# RefPoint01-01.net
KiCad netlist of a schematic drawn in Altium Designer
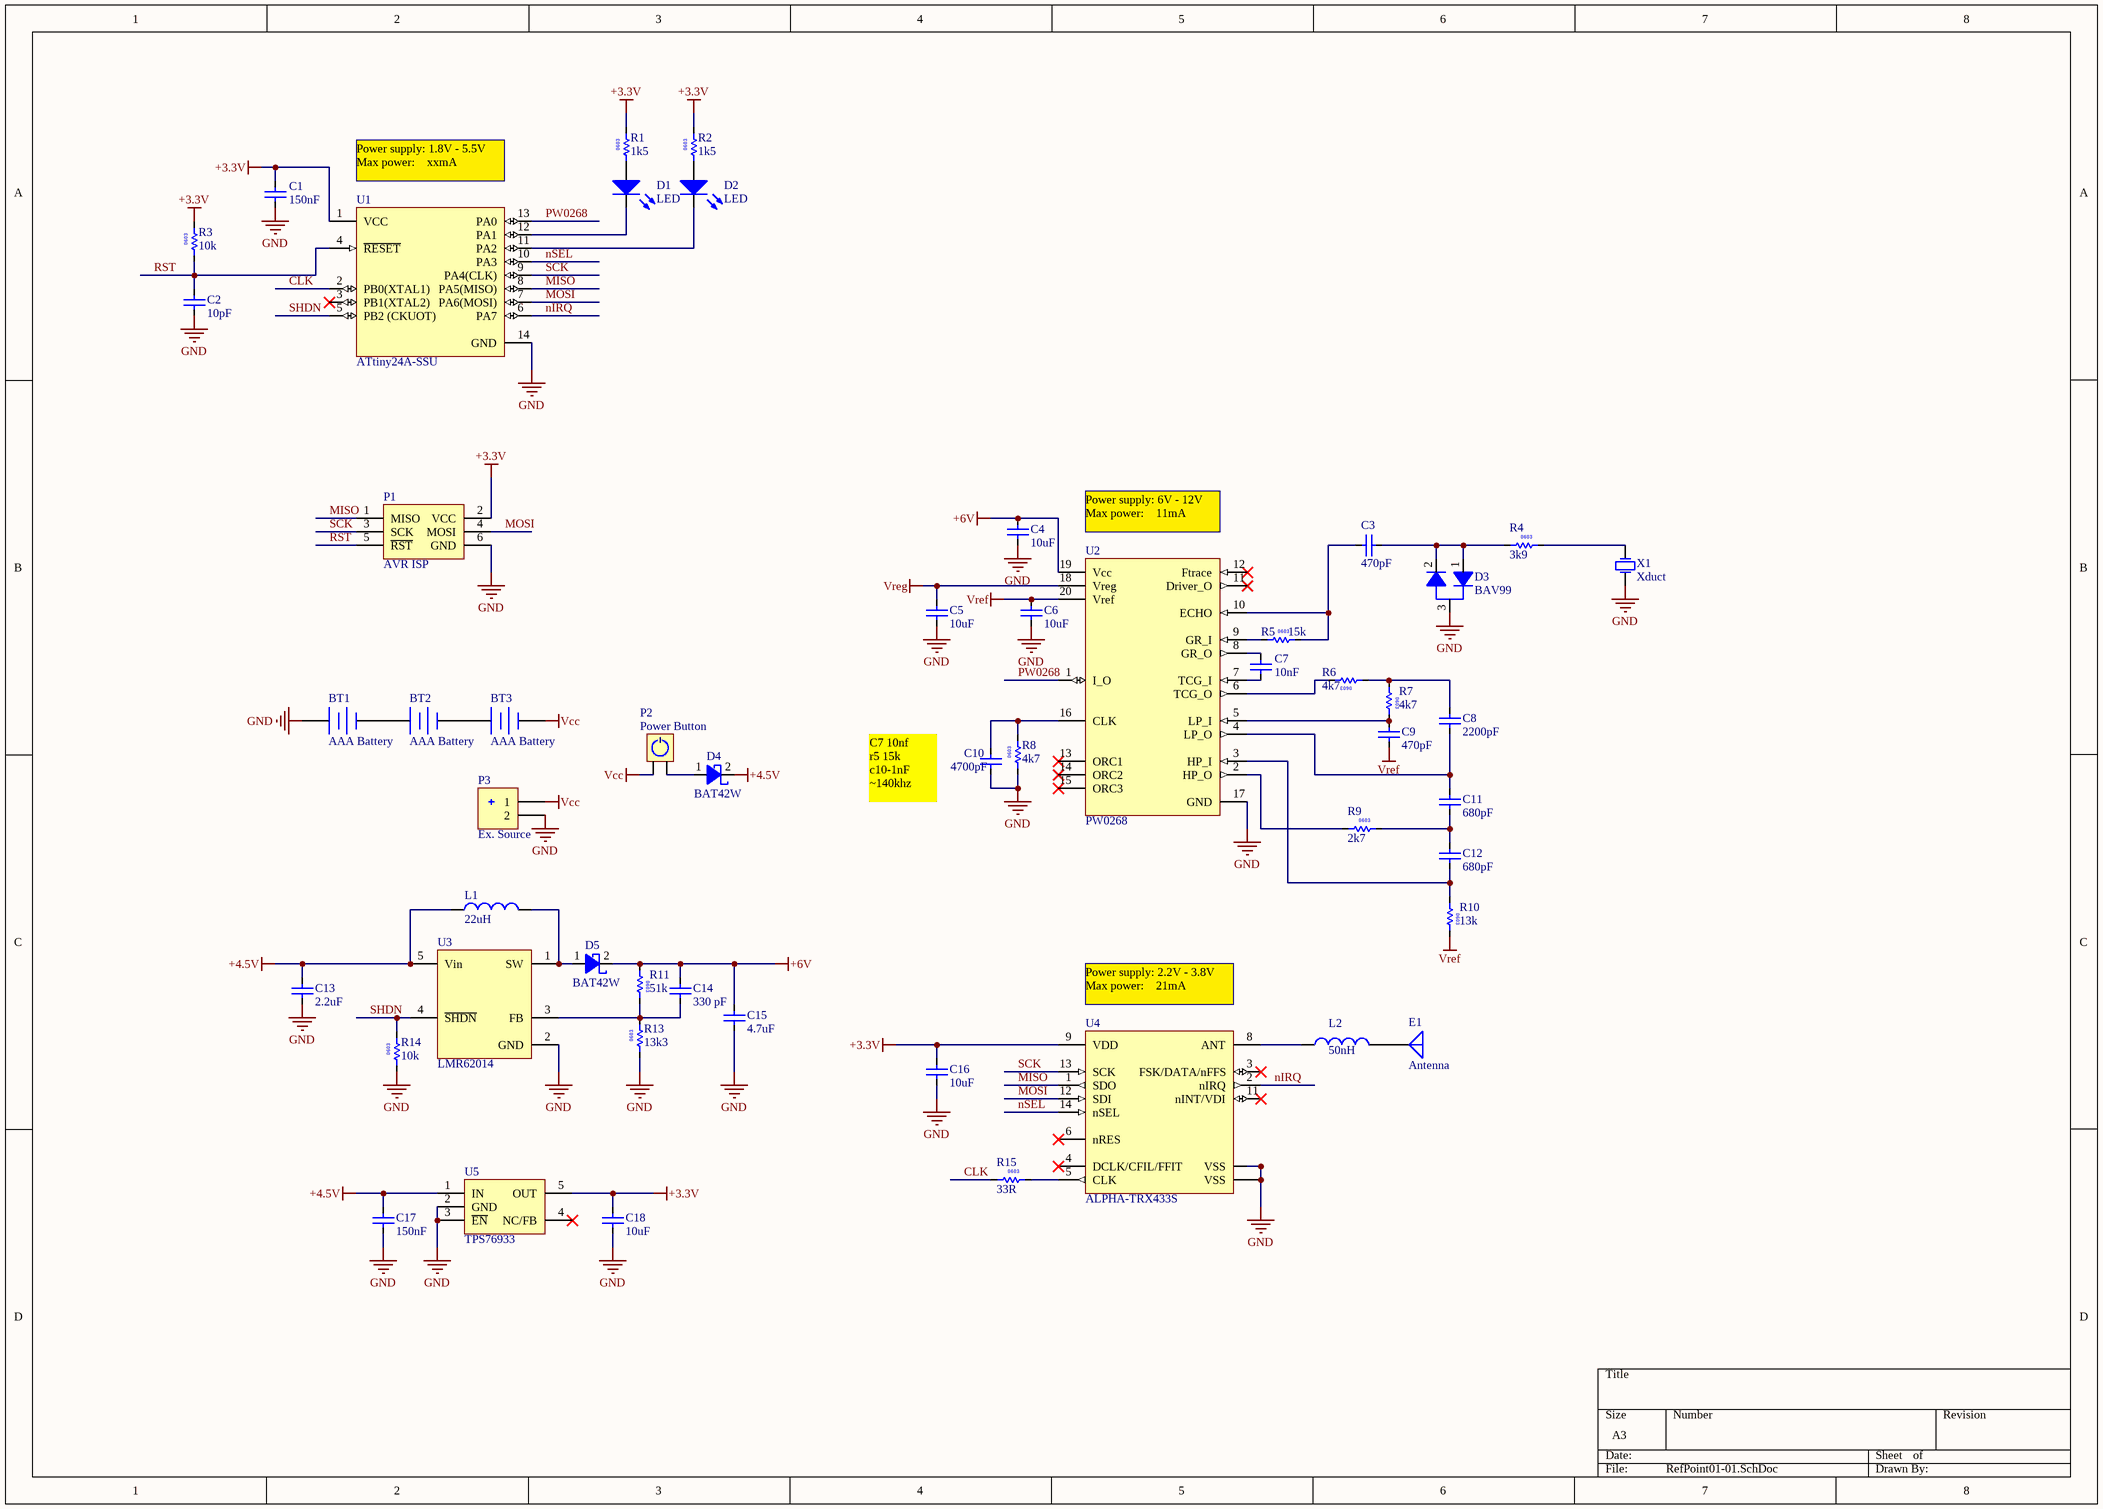
[diagram p0: RefPoint01-01.SchDoc]

(export (version "E")
  (design (tool "Eeschema 10.0.6"))
  (components
    (comp (ref "BT1")
      (value "AAA Battery")
      (footprint "Keystone 55 AAA CLIP")
      (description "Battery AAA")
      (fields (field (name "MANUFACTURER") "KEYSTONE") (field (name "MANUFACTURER PART NUMBER") "55"))
      (libsource (lib "UserSchlib") (part "Battery_AAA"))
    )
    (comp (ref "BT2")
      (value "AAA Battery")
      (footprint "Keystone 55 AAA CLIP")
      (description "Battery AAA")
      (fields (field (name "MANUFACTURER") "KEYSTONE") (field (name "MANUFACTURER PART NUMBER") "55"))
      (libsource (lib "UserSchlib") (part "Battery_AAA"))
    )
    (comp (ref "BT3")
      (value "AAA Battery")
      (footprint "Keystone 55 AAA CLIP")
      (description "Battery AAA")
      (fields (field (name "MANUFACTURER") "KEYSTONE") (field (name "MANUFACTURER PART NUMBER") "55"))
      (libsource (lib "UserSchlib") (part "Battery_AAA"))
    )
    (comp (ref "C1")
      (value "150nF")
      (footprint "CAPC1608N")
      (description "MLCC, 150nF 16V -20+80% Y5V")
      (fields (field (name "PART NUMBER") "C0000001") (field (name "VOLTAGE") "16"))
      (libsource (lib "KTU_DB") (part "C_SM"))
    )
    (comp (ref "C2")
      (value "10pF")
      (footprint "CAPC1608N")
      (description "MLCC, 0603, NP0, 50V, 10PF")
      (fields (field (name "PART NUMBER") "C0000042") (field (name "VOLTAGE") "100"))
      (libsource (lib "KTU_DB") (part "C_SM"))
    )
    (comp (ref "C3")
      (value "470pF")
      (footprint "CAPC1608N")
      (description "MLCC, 470pF 50V C0G 5% 0603")
      (fields (field (name "PART NUMBER") "C0000062") (field (name "VOLTAGE") "50"))
      (libsource (lib "KTU_DB") (part "C_SM"))
    )
    (comp (ref "C4")
      (value "10uF")
      (footprint "CAPC3216N")
      (description "MLCC, 10uF 25V -20%, +80% Y5V 1206")
      (fields (field (name "PART NUMBER") "C0000011") (field (name "VOLTAGE") "25"))
      (libsource (lib "KTU_DB") (part "C_SM"))
    )
    (comp (ref "C5")
      (value "10uF")
      (footprint "CAPC3216N")
      (description "MLCC, 10uF 25V -20%, +80% Y5V 1206")
      (fields (field (name "PART NUMBER") "C0000011") (field (name "VOLTAGE") "25"))
      (libsource (lib "KTU_DB") (part "C_SM"))
    )
    (comp (ref "C6")
      (value "10uF")
      (footprint "CAPC3216N")
      (description "MLCC, 10uF 25V -20%, +80% Y5V 1206")
      (fields (field (name "PART NUMBER") "C0000011") (field (name "VOLTAGE") "25"))
      (libsource (lib "KTU_DB") (part "C_SM"))
    )
    (comp (ref "C7")
      (value "10nF")
      (footprint "CAPC1608N")
      (description "MLCC, 0603, NP0, 50V, 10PF")
      (fields (field (name "PART NUMBER") "C0000042") (field (name "VOLTAGE") "100"))
      (libsource (lib "KTU_DB") (part "C_SM"))
    )
    (comp (ref "C8")
      (value "2200pF")
      (footprint "CAPC1608N")
      (description "MLCC, 2200pF 50V X7R 5% 0603")
      (fields (field (name "PART NUMBER") "C0000126") (field (name "VOLTAGE") "50"))
      (libsource (lib "KTU_DB") (part "C_SM"))
    )
    (comp (ref "C9")
      (value "470pF")
      (footprint "CAPC1608N")
      (description "MLCC, 470pF 50V C0G 5% 0603")
      (fields (field (name "PART NUMBER") "C0000062") (field (name "VOLTAGE") "50"))
      (libsource (lib "KTU_DB") (part "C_SM"))
    )
    (comp (ref "C10")
      (value "4700pF")
      (footprint "CAPC1608N")
      (description "MLCC, 4700pF 50V X7R 5% 0603")
      (fields (field (name "PART NUMBER") "C0000127") (field (name "VOLTAGE") "50"))
      (libsource (lib "KTU_DB") (part "C_SM"))
    )
    (comp (ref "C11")
      (value "680pF")
      (footprint "CAPC1608N")
      (description "MLCC, 680pF 50V C0G / NP0 5% 0603")
      (fields (field (name "PART NUMBER") "C0000125") (field (name "VOLTAGE") "50"))
      (libsource (lib "KTU_DB") (part "C_SM"))
    )
    (comp (ref "C12")
      (value "680pF")
      (footprint "CAPC1608N")
      (description "MLCC, 680pF 50V C0G / NP0 5% 0603")
      (fields (field (name "PART NUMBER") "C0000125") (field (name "VOLTAGE") "50"))
      (libsource (lib "KTU_DB") (part "C_SM"))
    )
    (comp (ref "C13")
      (value "2.2uF")
      (footprint "CAPC2012N")
      (description "MLCC, 2.2uF 16V X7R 0805")
      (fields (field (name "PART NUMBER") "C0000129") (field (name "VOLTAGE") "16V"))
      (libsource (lib "KTU_DB") (part "C_SM"))
    )
    (comp (ref "C14")
      (value "330 pF")
      (footprint "CAPC1608N")
      (description "MLCC, 50V, 330pF, 10%, X7R, 0603")
      (fields (field (name "PART NUMBER") "C0000018") (field (name "VOLTAGE") "50"))
      (libsource (lib "KTU_DB") (part "C_SM"))
    )
    (comp (ref "C15")
      (value "4.7uF")
      (footprint "CAPC3225N")
      (description "MLCC, 4.7uF 16V X7R 1210")
      (fields (field (name "PART NUMBER") "C0000130") (field (name "VOLTAGE") "50V"))
      (libsource (lib "KTU_DB") (part "C_SM"))
    )
    (comp (ref "C16")
      (value "10uF")
      (footprint "CAPC3216N")
      (description "MLCC, 10uF 25V -20%, +80% Y5V 1206")
      (fields (field (name "PART NUMBER") "C0000011") (field (name "VOLTAGE") "25"))
      (libsource (lib "KTU_DB") (part "C_SM"))
    )
    (comp (ref "C17")
      (value "150nF")
      (footprint "CAPC1608N")
      (description "MLCC, 150nF 16V -20+80% Y5V")
      (fields (field (name "PART NUMBER") "C0000001") (field (name "VOLTAGE") "16"))
      (libsource (lib "KTU_DB") (part "C_SM"))
    )
    (comp (ref "C18")
      (value "10uF")
      (footprint "CAPC3216N")
      (description "MLCC, 10uF 25V -20%, +80% Y5V 1206")
      (fields (field (name "PART NUMBER") "C0000011") (field (name "VOLTAGE") "25"))
      (libsource (lib "KTU_DB") (part "C_SM"))
    )
    (comp (ref "D1")
      (value "LED")
      (footprint "LED 3mm DIP")
      (description "Typical INFRARED GaAs LED")
      (fields (field (name "PUBLISHER") "Altium Limited"))
      (libsource (lib "UserSchlib") (part "LED0"))
    )
    (comp (ref "D2")
      (value "LED")
      (footprint "LED 3mm DIP")
      (description "Typical INFRARED GaAs LED")
      (fields (field (name "PUBLISHER") "Altium Limited"))
      (libsource (lib "UserSchlib") (part "LED0"))
    )
    (comp (ref "D3")
      (value "BAV99")
      (footprint "SOT95P240-3L")
      (description "DIODE SW DUAL 75V 350mW SOT23")
      (fields (field (name "PART NUMBER") "D0000001") (field (name "MANUFACTURER") "ON SEMICONDUCTOR"))
      (libsource (lib "KTU_DB") (part "BAV99"))
    )
    (comp (ref "D4")
      (value "BAT42W")
      (footprint "SOD123")
      (description "Diode Schottkey, 30V, Vf=1V, If=1A, rrt=5ns, SOD123, -55°C to +125°C")
      (fields (field (name "PART NUMBER") "D0000003") (field (name "MANUFACTURER") "VISHAY SEMICONDUCTOR"))
      (libsource (lib "KTU_DB") (part "Diode_SCHOTTKY"))
    )
    (comp (ref "D5")
      (value "BAT42W")
      (footprint "SOD123")
      (description "Diode Schottkey, 30V, Vf=1V, If=1A, rrt=5ns, SOD123, -55°C to +125°C")
      (fields (field (name "PART NUMBER") "D0000003") (field (name "MANUFACTURER") "VISHAY SEMICONDUCTOR"))
      (libsource (lib "KTU_DB") (part "Diode_SCHOTTKY"))
    )
    (comp (ref "E1")
      (value "Antenna")
      (description "Generic Antenna")
      (fields (field (name "PUBLISHER") "Altium Limited"))
      (libsource (lib "Miscellaneous Devices") (part "Antenna"))
    )
    (comp (ref "L1")
      (value "22uH")
      (footprint "INDM7070x32N")
      (description "Inductor")
      (fields
        (field (name "MANUFACTURER PART NUMBER") "810-SLF732220MR962PF")
        (field (name "MANUFACTURER") "TDK")
      )
      (libsource (lib "UserSchlib") (part "L Inductor 810-SLF732220MR962PF"))
    )
    (comp (ref "L2")
      (value "50nH")
      (footprint "INDC2012L")
      (description "Inductor")
      (fields (field (name "PUBLISHER") "Altium Limited"))
      (libsource (lib "Miscellaneous Devices") (part "Inductor"))
    )
    (comp (ref "P1")
      (value "AVR ISP")
      (footprint "HDR2X3")
      (description "Header, 6-Pin")
      (fields (field (name "PUBLISHER") "Altium Limited"))
      (libsource (lib "Arthur Shematic") (part "AVR ISP"))
    )
    (comp (ref "P2")
      (value "Power Button")
      (footprint "HDR1X2")
      (description "Header, 2-Pin, Right Angle")
      (fields (field (name "PUBLISHER") "Altium Limited"))
      (libsource (lib "UserSchlib") (part "Power Button"))
    )
    (comp (ref "P3")
      (value "Ex. Source")
      (footprint "HDR1X2")
      (description "Header, 2-Pin")
      (fields (field (name "PUBLISHER") "Altium Limited"))
      (libsource (lib "Arthur Shematic") (part "Maitinimas"))
    )
    (comp (ref "R1")
      (value "1k5")
      (footprint "RESC1608N")
      (description "1K5 5% 0603 1/10W")
      (fields (field (name "TOLERANCE") "±5%") (field (name "POWER") "1/10W"))
      (libsource (lib "KTU_DB") (part "R0603"))
    )
    (comp (ref "R2")
      (value "1k5")
      (footprint "RESC1608N")
      (description "1K5 5% 0603 1/10W")
      (fields (field (name "TOLERANCE") "±5%") (field (name "POWER") "1/10W"))
      (libsource (lib "KTU_DB") (part "R0603"))
    )
    (comp (ref "R3")
      (value "10k")
      (footprint "RESC1608N")
      (description "Res, 10K 0.063W 75V 1%  0603")
      (fields (field (name "TOLERANCE") "±1%") (field (name "POWER") "0.063W"))
      (libsource (lib "KTU_DB") (part "R0603"))
    )
    (comp (ref "R4")
      (value "3k9")
      (footprint "RESC1608N")
      (description "3K9 5% 0603 1/10W")
      (fields (field (name "TOLERANCE") "±5%") (field (name "POWER") "1/10W"))
      (libsource (lib "KTU_DB") (part "R0603"))
    )
    (comp (ref "R5")
      (value "15k")
      (footprint "RESC1608N")
      (description "300K 5% 0603 1/10W")
      (fields (field (name "TOLERANCE") "±5%") (field (name "POWER") "1/10W"))
      (libsource (lib "KTU_DB") (part "R0603"))
    )
    (comp (ref "R6")
      (value "4k7")
      (footprint "RESC1608N")
      (description "Res, 4K7 5% 0603 1/10W")
      (fields (field (name "TOLERANCE") "±5%") (field (name "POWER") "1/10W"))
      (libsource (lib "KTU_DB") (part "R0603"))
    )
    (comp (ref "R7")
      (value "4k7")
      (footprint "RESC1608N")
      (description "Res, 4K7 5% 0603 1/10W")
      (fields (field (name "TOLERANCE") "±5%") (field (name "POWER") "1/10W"))
      (libsource (lib "KTU_DB") (part "R0603"))
    )
    (comp (ref "R8")
      (value "4k7")
      (footprint "RESC1608N")
      (description "Res, 4K7 5% 0603 1/10W")
      (fields (field (name "TOLERANCE") "±5%") (field (name "POWER") "1/10W"))
      (libsource (lib "KTU_DB") (part "R0603"))
    )
    (comp (ref "R9")
      (value "2k7")
      (footprint "RESC1608N")
      (description "2K7 5% 0603 1/10W")
      (fields (field (name "TOLERANCE") "±5%") (field (name "POWER") "1/10W"))
      (libsource (lib "KTU_DB") (part "R0603"))
    )
    (comp (ref "R10")
      (value "13k")
      (footprint "RESC1608N")
      (description "13K 5% 0603 1/10W")
      (fields (field (name "TOLERANCE") "±5%") (field (name "POWER") "1/10W"))
      (libsource (lib "KTU_DB") (part "R0603"))
    )
    (comp (ref "R11")
      (value "51k")
      (footprint "RESC1608X50N")
      (description "Res, 51K, 0603 (1608 metric), ±1%, 100mW, 75V")
      (fields (field (name "TOLERANCE") "±1%") (field (name "POWER") "100mW"))
      (libsource (lib "KTU_DB") (part "R0603"))
    )
    (comp (ref "R13")
      (value "13k3")
      (footprint "RESC1608X50N")
      (description "Res, 13K3, 0603 (1608 metric), ±1%, 100mW, 75V")
      (fields (field (name "TOLERANCE") "±1%") (field (name "POWER") "100mW"))
      (libsource (lib "KTU_DB") (part "R0603"))
    )
    (comp (ref "R14")
      (value "10k")
      (footprint "RESC1608X50N")
      (description "Res, 10K, 0603 (1608 metric), ±1%, 100mW, 75V")
      (libsource (lib "KTU_DB") (part "R0603"))
    )
    (comp (ref "R15")
      (value "33R")
      (footprint "RESC1608X50N")
      (description "Res, 33R, 0603 (1608 metric), ±1%, 100mW, 75V")
      (libsource (lib "KTU_DB") (part "R0603"))
    )
    (comp (ref "U1")
      (value "ATtiny24A-SSU")
      (footprint "UserPcbLib:SOIC14T_L")
      (fields (field (name "MANUFACTURER") "Atmel"))
      (libsource (lib "UserSchlib") (part "ATtiny24A-SSU"))
    )
    (comp (ref "U2")
      (value "PW0268")
      (footprint "QSSOP20_0.635/4.0X8.7")
      (fields (field (name "MANUFACTURER") "PROWAVE"))
      (libsource (lib "UserSchlib") (part "PW0268"))
    )
    (comp (ref "U3")
      (value "LMR62014")
      (footprint "SOT23-5AM")
      (description "2064695")
      (fields
        (field (name "MANUFACTURER PART NUMBER") "LMR62014XMFE")
        (field (name "MANUFACTURER") "TEXAS INSTRUMENTS")
      )
      (libsource (lib "UserSchlib") (part "LMR62014"))
    )
    (comp (ref "U4")
      (value "ALPHA-TRX433S")
      (footprint "ALPHA-TRX")
      (description "RF SOLUTIONS  ALPHA-TRX433S  RF MODULE, TRANSCEIVER, FSK, 433MHZ")
      (fields (field (name "MANUFACTURER") "RF SOLUTIONS"))
      (libsource (lib "UserSchlib") (part "ALPHA-TRX433S"))
    )
    (comp (ref "U5")
      (value "TPS76933")
      (footprint "SOT23-5AM")
      (description "ULTRALOW-POWER 100-mA LOW-DROPOUT LINEAR REGULATORS")
      (fields
        (field (name "MANUFACTURER PART NUMBER") "TPS76933DBVT")
        (field (name "MANUFACTURER") "TEXAS INSTRUMENTS")
      )
      (libsource (lib "UserSchlib") (part "TPS769xx"))
    )
    (comp (ref "X1")
      (value "Xduct")
      (footprint "Xducts1")
      (description "Transducer")
      (libsource (lib "UserSchlib") (part "Xduct1"))
    )
  )
  (nets
    (net (code "1") (name "+3.3V") (class "Default")
      (node (ref "C1") (pin "2") (pinfunction "2_2") (pintype "passive"))
      (node (ref "C16") (pin "2") (pinfunction "2_2") (pintype "passive"))
      (node (ref "C18") (pin "2") (pinfunction "2_2") (pintype "passive"))
      (node (ref "P1") (pin "2") (pinfunction "VCC_2") (pintype "passive"))
      (node (ref "R1") (pin "2") (pinfunction "2_2") (pintype "passive"))
      (node (ref "R2") (pin "2") (pinfunction "2_2") (pintype "passive"))
      (node (ref "R3") (pin "2") (pinfunction "2_2") (pintype "passive"))
      (node (ref "U1") (pin "1") (pinfunction "VCC_1") (pintype "power_in"))
      (node (ref "U4") (pin "9") (pinfunction "VDD_9") (pintype "power_in"))
      (node (ref "U5") (pin "5") (pinfunction "OUT_5") (pintype "power_in"))
    )
    (net (code "2") (name "+4.5V") (class "Default")
      (node (ref "C13") (pin "2") (pinfunction "2_2") (pintype "passive"))
      (node (ref "C17") (pin "2") (pinfunction "2_2") (pintype "passive"))
      (node (ref "D4") (pin "2") (pinfunction "CATHODE_2") (pintype "passive"))
      (node (ref "L1") (pin "2") (pinfunction "2_2") (pintype "passive"))
      (node (ref "U3") (pin "5") (pinfunction "Vin_5") (pintype "passive"))
      (node (ref "U5") (pin "1") (pinfunction "IN_1") (pintype "power_in"))
    )
    (net (code "3") (name "+6V") (class "Default")
      (node (ref "C14") (pin "2") (pinfunction "2_2") (pintype "passive"))
      (node (ref "C15") (pin "2") (pinfunction "2_2") (pintype "passive"))
      (node (ref "C4") (pin "2") (pinfunction "2_2") (pintype "passive"))
      (node (ref "D5") (pin "2") (pinfunction "CATHODE_2") (pintype "passive"))
      (node (ref "R11") (pin "1") (pinfunction "1_1") (pintype "passive"))
      (node (ref "U2") (pin "19") (pinfunction "Vcc_19") (pintype "power_in"))
    )
    (net (code "4") (name "/CLK") (class "Default")
      (node (ref "R15") (pin "1") (pinfunction "1_1") (pintype "passive"))
      (node (ref "U1") (pin "2") (pinfunction "PB0(XTAL1)_2") (pintype "bidirectional"))
    )
    (net (code "5") (name "/MISO") (class "Default")
      (node (ref "P1") (pin "1") (pinfunction "MISO_1") (pintype "passive"))
      (node (ref "U1") (pin "8") (pinfunction "PA5(MISO)_8") (pintype "bidirectional"))
      (node (ref "U4") (pin "1") (pinfunction "SDO_1") (pintype "output"))
    )
    (net (code "6") (name "/MOSI") (class "Default")
      (node (ref "P1") (pin "4") (pinfunction "MOSI_4") (pintype "passive"))
      (node (ref "U1") (pin "7") (pinfunction "PA6(MOSI)_7") (pintype "bidirectional"))
      (node (ref "U4") (pin "12") (pinfunction "SDI_12") (pintype "input"))
    )
    (net (code "7") (name "/PW0268") (class "Default")
      (node (ref "U1") (pin "13") (pinfunction "PA0_13") (pintype "bidirectional"))
      (node (ref "U2") (pin "1") (pinfunction "I_O_1") (pintype "bidirectional"))
    )
    (net (code "8") (name "/RST") (class "Default")
      (node (ref "C2") (pin "2") (pinfunction "2_2") (pintype "passive"))
      (node (ref "P1") (pin "5") (pinfunction "~{RST}_5") (pintype "passive"))
      (node (ref "R3") (pin "1") (pinfunction "1_1") (pintype "passive"))
      (node (ref "U1") (pin "4") (pinfunction "~{RESET}_4") (pintype "input"))
    )
    (net (code "9") (name "/SCK") (class "Default")
      (node (ref "P1") (pin "3") (pinfunction "SCK_3") (pintype "passive"))
      (node (ref "U1") (pin "9") (pinfunction "PA4(CLK)_9") (pintype "bidirectional"))
      (node (ref "U4") (pin "13") (pinfunction "SCK_13") (pintype "input"))
    )
    (net (code "10") (name "/SHDN") (class "Default")
      (node (ref "R14") (pin "2") (pinfunction "2_2") (pintype "passive"))
      (node (ref "U1") (pin "5") (pinfunction "PB2_(CKUOT)_5") (pintype "bidirectional"))
      (node (ref "U3") (pin "4") (pinfunction "~{SHDN}_4") (pintype "passive"))
    )
    (net (code "11") (name "/nIRQ") (class "Default")
      (node (ref "U1") (pin "6") (pinfunction "PA7_6") (pintype "bidirectional"))
      (node (ref "U4") (pin "2") (pinfunction "nIRQ_2") (pintype "output"))
    )
    (net (code "12") (name "/nSEL") (class "Default")
      (node (ref "U1") (pin "10") (pinfunction "PA3_10") (pintype "bidirectional"))
      (node (ref "U4") (pin "14") (pinfunction "nSEL_14") (pintype "input"))
    )
    (net (code "13") (name "GND") (class "Default")
      (node (ref "BT1") (pin "1") (pinfunction "+_1") (pintype "passive"))
      (node (ref "C1") (pin "1") (pinfunction "1_1") (pintype "passive"))
      (node (ref "C10") (pin "1") (pinfunction "1_1") (pintype "passive"))
      (node (ref "C13") (pin "1") (pinfunction "1_1") (pintype "passive"))
      (node (ref "C15") (pin "1") (pinfunction "1_1") (pintype "passive"))
      (node (ref "C16") (pin "1") (pinfunction "1_1") (pintype "passive"))
      (node (ref "C17") (pin "1") (pinfunction "1_1") (pintype "passive"))
      (node (ref "C18") (pin "1") (pinfunction "1_1") (pintype "passive"))
      (node (ref "C2") (pin "1") (pinfunction "1_1") (pintype "passive"))
      (node (ref "C4") (pin "1") (pinfunction "1_1") (pintype "passive"))
      (node (ref "C5") (pin "1") (pinfunction "1_1") (pintype "passive"))
      (node (ref "C6") (pin "1") (pinfunction "1_1") (pintype "passive"))
      (node (ref "D3") (pin "3") (pinfunction "K_3") (pintype "passive"))
      (node (ref "P1") (pin "6") (pinfunction "GND_6") (pintype "passive"))
      (node (ref "P3") (pin "2") (pinfunction "2_2") (pintype "passive"))
      (node (ref "R13") (pin "1") (pinfunction "1_1") (pintype "passive"))
      (node (ref "R14") (pin "1") (pinfunction "1_1") (pintype "passive"))
      (node (ref "R8") (pin "1") (pinfunction "1_1") (pintype "passive"))
      (node (ref "U1") (pin "14") (pinfunction "GND_14") (pintype "power_in"))
      (node (ref "U2") (pin "17") (pinfunction "GND_17") (pintype "power_in"))
      (node (ref "U3") (pin "2") (pinfunction "GND_2") (pintype "passive"))
      (node (ref "U4") (pin "10") (pinfunction "VSS_10") (pintype "power_in"))
      (node (ref "U4") (pin "7") (pinfunction "VSS_7") (pintype "power_in"))
      (node (ref "U5") (pin "2") (pinfunction "GND_2") (pintype "power_in"))
      (node (ref "U5") (pin "3") (pinfunction "~{EN}_3") (pintype "power_in"))
      (node (ref "X1") (pin "2") (pinfunction "2_2") (pintype "passive"))
    )
    (net (code "14") (name "Net-(BT1--)") (class "Default")
      (node (ref "BT1") (pin "2") (pinfunction "-_2") (pintype "passive"))
      (node (ref "BT2") (pin "1") (pinfunction "+_1") (pintype "passive"))
    )
    (net (code "15") (name "Net-(BT2--)") (class "Default")
      (node (ref "BT2") (pin "2") (pinfunction "-_2") (pintype "passive"))
      (node (ref "BT3") (pin "1") (pinfunction "+_1") (pintype "passive"))
    )
    (net (code "16") (name "Net-(C8-Pad2)") (class "Default")
      (node (ref "C8") (pin "2") (pinfunction "2_2") (pintype "passive"))
      (node (ref "R6") (pin "1") (pinfunction "1_1") (pintype "passive"))
      (node (ref "R7") (pin "1") (pinfunction "1_1") (pintype "passive"))
    )
    (net (code "17") (name "Net-(C11-Pad2)") (class "Default")
      (node (ref "C11") (pin "2") (pinfunction "2_2") (pintype "passive"))
      (node (ref "C12") (pin "1") (pinfunction "1_1") (pintype "passive"))
      (node (ref "R9") (pin "2") (pinfunction "2_2") (pintype "passive"))
    )
    (net (code "18") (name "Net-(D1-A)") (class "Default")
      (node (ref "D1") (pin "1") (pinfunction "A_1") (pintype "passive"))
      (node (ref "R1") (pin "1") (pinfunction "1_1") (pintype "passive"))
    )
    (net (code "19") (name "Net-(D1-K)") (class "Default")
      (node (ref "D1") (pin "2") (pinfunction "K_2") (pintype "passive"))
      (node (ref "U1") (pin "12") (pinfunction "PA1_12") (pintype "bidirectional"))
    )
    (net (code "20") (name "Net-(D2-A)") (class "Default")
      (node (ref "D2") (pin "1") (pinfunction "A_1") (pintype "passive"))
      (node (ref "R2") (pin "1") (pinfunction "1_1") (pintype "passive"))
    )
    (net (code "21") (name "Net-(D2-K)") (class "Default")
      (node (ref "D2") (pin "2") (pinfunction "K_2") (pintype "passive"))
      (node (ref "U1") (pin "11") (pinfunction "PA2_11") (pintype "bidirectional"))
    )
    (net (code "22") (name "Net-(D3-A)") (class "Default")
      (node (ref "C3") (pin "2") (pinfunction "2_2") (pintype "passive"))
      (node (ref "D3") (pin "1") (pinfunction "A1_1") (pintype "passive"))
      (node (ref "D3") (pin "2") (pinfunction "A_2") (pintype "passive"))
      (node (ref "R4") (pin "1") (pinfunction "1_1") (pintype "passive"))
    )
    (net (code "23") (name "Net-(D4-ANODE)") (class "Default")
      (node (ref "D4") (pin "1") (pinfunction "ANODE_1") (pintype "passive"))
      (node (ref "P2") (pin "2") (pinfunction "2_2") (pintype "passive"))
    )
    (net (code "24") (name "Net-(D5-ANODE)") (class "Default")
      (node (ref "D5") (pin "1") (pinfunction "ANODE_1") (pintype "passive"))
      (node (ref "L1") (pin "1") (pinfunction "1_1") (pintype "passive"))
      (node (ref "U3") (pin "1") (pinfunction "SW_1") (pintype "passive"))
    )
    (net (code "25") (name "Net-(E1-A)") (class "Default")
      (node (ref "E1") (pin "1") (pinfunction "A_1") (pintype "passive"))
      (node (ref "L2") (pin "2") (pinfunction "2_2") (pintype "passive"))
    )
    (net (code "26") (name "Net-(R4-Pad2)") (class "Default")
      (node (ref "R4") (pin "2") (pinfunction "2_2") (pintype "passive"))
      (node (ref "X1") (pin "1") (pinfunction "1_1") (pintype "passive"))
    )
    (net (code "27") (name "Net-(U2-CLK)") (class "Default")
      (node (ref "C10") (pin "2") (pinfunction "2_2") (pintype "passive"))
      (node (ref "R8") (pin "2") (pinfunction "2_2") (pintype "passive"))
      (node (ref "U2") (pin "16") (pinfunction "CLK_16") (pintype "passive"))
    )
    (net (code "28") (name "Net-(U2-ECHO)") (class "Default")
      (node (ref "C3") (pin "1") (pinfunction "1_1") (pintype "passive"))
      (node (ref "R5") (pin "2") (pinfunction "2_2") (pintype "passive"))
      (node (ref "U2") (pin "10") (pinfunction "ECHO_10") (pintype "input"))
    )
    (net (code "29") (name "Net-(U2-GR_I)") (class "Default")
      (node (ref "R5") (pin "1") (pinfunction "1_1") (pintype "passive"))
      (node (ref "U2") (pin "9") (pinfunction "GR_I_9") (pintype "input"))
    )
    (net (code "30") (name "Net-(U2-GR_O)") (class "Default")
      (node (ref "C7") (pin "1") (pinfunction "1_1") (pintype "passive"))
      (node (ref "U2") (pin "8") (pinfunction "GR_O_8") (pintype "output"))
    )
    (net (code "31") (name "Net-(U2-HP_I)") (class "Default")
      (node (ref "C12") (pin "2") (pinfunction "2_2") (pintype "passive"))
      (node (ref "R10") (pin "1") (pinfunction "1_1") (pintype "passive"))
      (node (ref "U2") (pin "3") (pinfunction "HP_I_3") (pintype "input"))
    )
    (net (code "32") (name "Net-(U2-HP_O)") (class "Default")
      (node (ref "R9") (pin "1") (pinfunction "1_1") (pintype "passive"))
      (node (ref "U2") (pin "2") (pinfunction "HP_O_2") (pintype "output"))
    )
    (net (code "33") (name "Net-(U2-LP_I)") (class "Default")
      (node (ref "C9") (pin "2") (pinfunction "2_2") (pintype "passive"))
      (node (ref "R7") (pin "2") (pinfunction "2_2") (pintype "passive"))
      (node (ref "U2") (pin "5") (pinfunction "LP_I_5") (pintype "input"))
    )
    (net (code "34") (name "Net-(U2-LP_O)") (class "Default")
      (node (ref "C11") (pin "1") (pinfunction "1_1") (pintype "passive"))
      (node (ref "C8") (pin "1") (pinfunction "1_1") (pintype "passive"))
      (node (ref "U2") (pin "4") (pinfunction "LP_O_4") (pintype "output"))
    )
    (net (code "35") (name "Net-(U2-TCG_I)") (class "Default")
      (node (ref "C7") (pin "2") (pinfunction "2_2") (pintype "passive"))
      (node (ref "U2") (pin "7") (pinfunction "TCG_I_7") (pintype "input"))
    )
    (net (code "36") (name "Net-(U2-TCG_O)") (class "Default")
      (node (ref "R6") (pin "2") (pinfunction "2_2") (pintype "passive"))
      (node (ref "U2") (pin "6") (pinfunction "TCG_O_6") (pintype "output"))
    )
    (net (code "37") (name "Net-(U3-FB)") (class "Default")
      (node (ref "C14") (pin "1") (pinfunction "1_1") (pintype "passive"))
      (node (ref "R11") (pin "2") (pinfunction "2_2") (pintype "passive"))
      (node (ref "R13") (pin "2") (pinfunction "2_2") (pintype "passive"))
      (node (ref "U3") (pin "3") (pinfunction "FB_3") (pintype "passive"))
    )
    (net (code "38") (name "Net-(U4-ANT)") (class "Default")
      (node (ref "L2") (pin "1") (pinfunction "1_1") (pintype "passive"))
      (node (ref "U4") (pin "8") (pinfunction "ANT_8") (pintype "passive"))
    )
    (net (code "39") (name "Net-(U4-CLK)") (class "Default")
      (node (ref "R15") (pin "2") (pinfunction "2_2") (pintype "passive"))
      (node (ref "U4") (pin "5") (pinfunction "CLK_5") (pintype "output"))
    )
    (net (code "40") (name "Vcc") (class "Default")
      (node (ref "BT3") (pin "2") (pinfunction "-_2") (pintype "passive"))
      (node (ref "P2") (pin "1") (pinfunction "1_1") (pintype "passive"))
      (node (ref "P3") (pin "1") (pinfunction "1_1") (pintype "passive"))
    )
    (net (code "41") (name "Vref") (class "Default")
      (node (ref "C6") (pin "2") (pinfunction "2_2") (pintype "passive"))
      (node (ref "C9") (pin "1") (pinfunction "1_1") (pintype "passive"))
      (node (ref "R10") (pin "2") (pinfunction "2_2") (pintype "passive"))
      (node (ref "U2") (pin "20") (pinfunction "Vref_20") (pintype "power_in"))
    )
    (net (code "42") (name "Vreg") (class "Default")
      (node (ref "C5") (pin "2") (pinfunction "2_2") (pintype "passive"))
      (node (ref "U2") (pin "18") (pinfunction "Vreg_18") (pintype "power_in"))
    )
    (net (code "43") (name "unconnected-(U1-PB1(XTAL2)-Pad3)") (class "Default")
      (node (ref "U1") (pin "3") (pinfunction "PB1(XTAL2)_3") (pintype "bidirectional+no_connect"))
    )
    (net (code "44") (name "unconnected-(U2-Driver_O-Pad11)") (class "Default")
      (node (ref "U2") (pin "11") (pinfunction "Driver_O_11") (pintype "output+no_connect"))
    )
    (net (code "45") (name "unconnected-(U2-Ftrace-Pad12)") (class "Default")
      (node (ref "U2") (pin "12") (pinfunction "Ftrace_12") (pintype "input+no_connect"))
    )
    (net (code "46") (name "unconnected-(U2-ORC1-Pad13)") (class "Default")
      (node (ref "U2") (pin "13") (pinfunction "ORC1_13") (pintype "passive+no_connect"))
    )
    (net (code "47") (name "unconnected-(U2-ORC2-Pad14)") (class "Default")
      (node (ref "U2") (pin "14") (pinfunction "ORC2_14") (pintype "passive+no_connect"))
    )
    (net (code "48") (name "unconnected-(U2-ORC3-Pad15)") (class "Default")
      (node (ref "U2") (pin "15") (pinfunction "ORC3_15") (pintype "passive+no_connect"))
    )
    (net (code "49") (name "unconnected-(U4-DCLK{slash}CFIL{slash}FFIT-Pad4)") (class "Default")
      (node (ref "U4") (pin "4") (pinfunction "DCLK/CFIL/FFIT_4") (pintype "passive+no_connect"))
    )
    (net (code "50") (name "unconnected-(U4-FSK{slash}DATA{slash}nFFS-Pad3)") (class "Default")
      (node (ref "U4") (pin "3") (pinfunction "FSK/DATA/nFFS_3") (pintype "bidirectional+no_connect"))
    )
    (net (code "51") (name "unconnected-(U4-nINT{slash}VDI-Pad11)") (class "Default")
      (node (ref "U4") (pin "11") (pinfunction "nINT/VDI_11") (pintype "bidirectional+no_connect"))
    )
    (net (code "52") (name "unconnected-(U4-nRES-Pad6)") (class "Default")
      (node (ref "U4") (pin "6") (pinfunction "nRES_6") (pintype "passive+no_connect"))
    )
    (net (code "53") (name "unconnected-(U5-NC{slash}FB-Pad4)") (class "Default")
      (node (ref "U5") (pin "4") (pinfunction "NC/FB_4") (pintype "power_in+no_connect"))
    )
  )
)
